# Schematic.net
KiCad netlist of a schematic drawn in Altium Designer
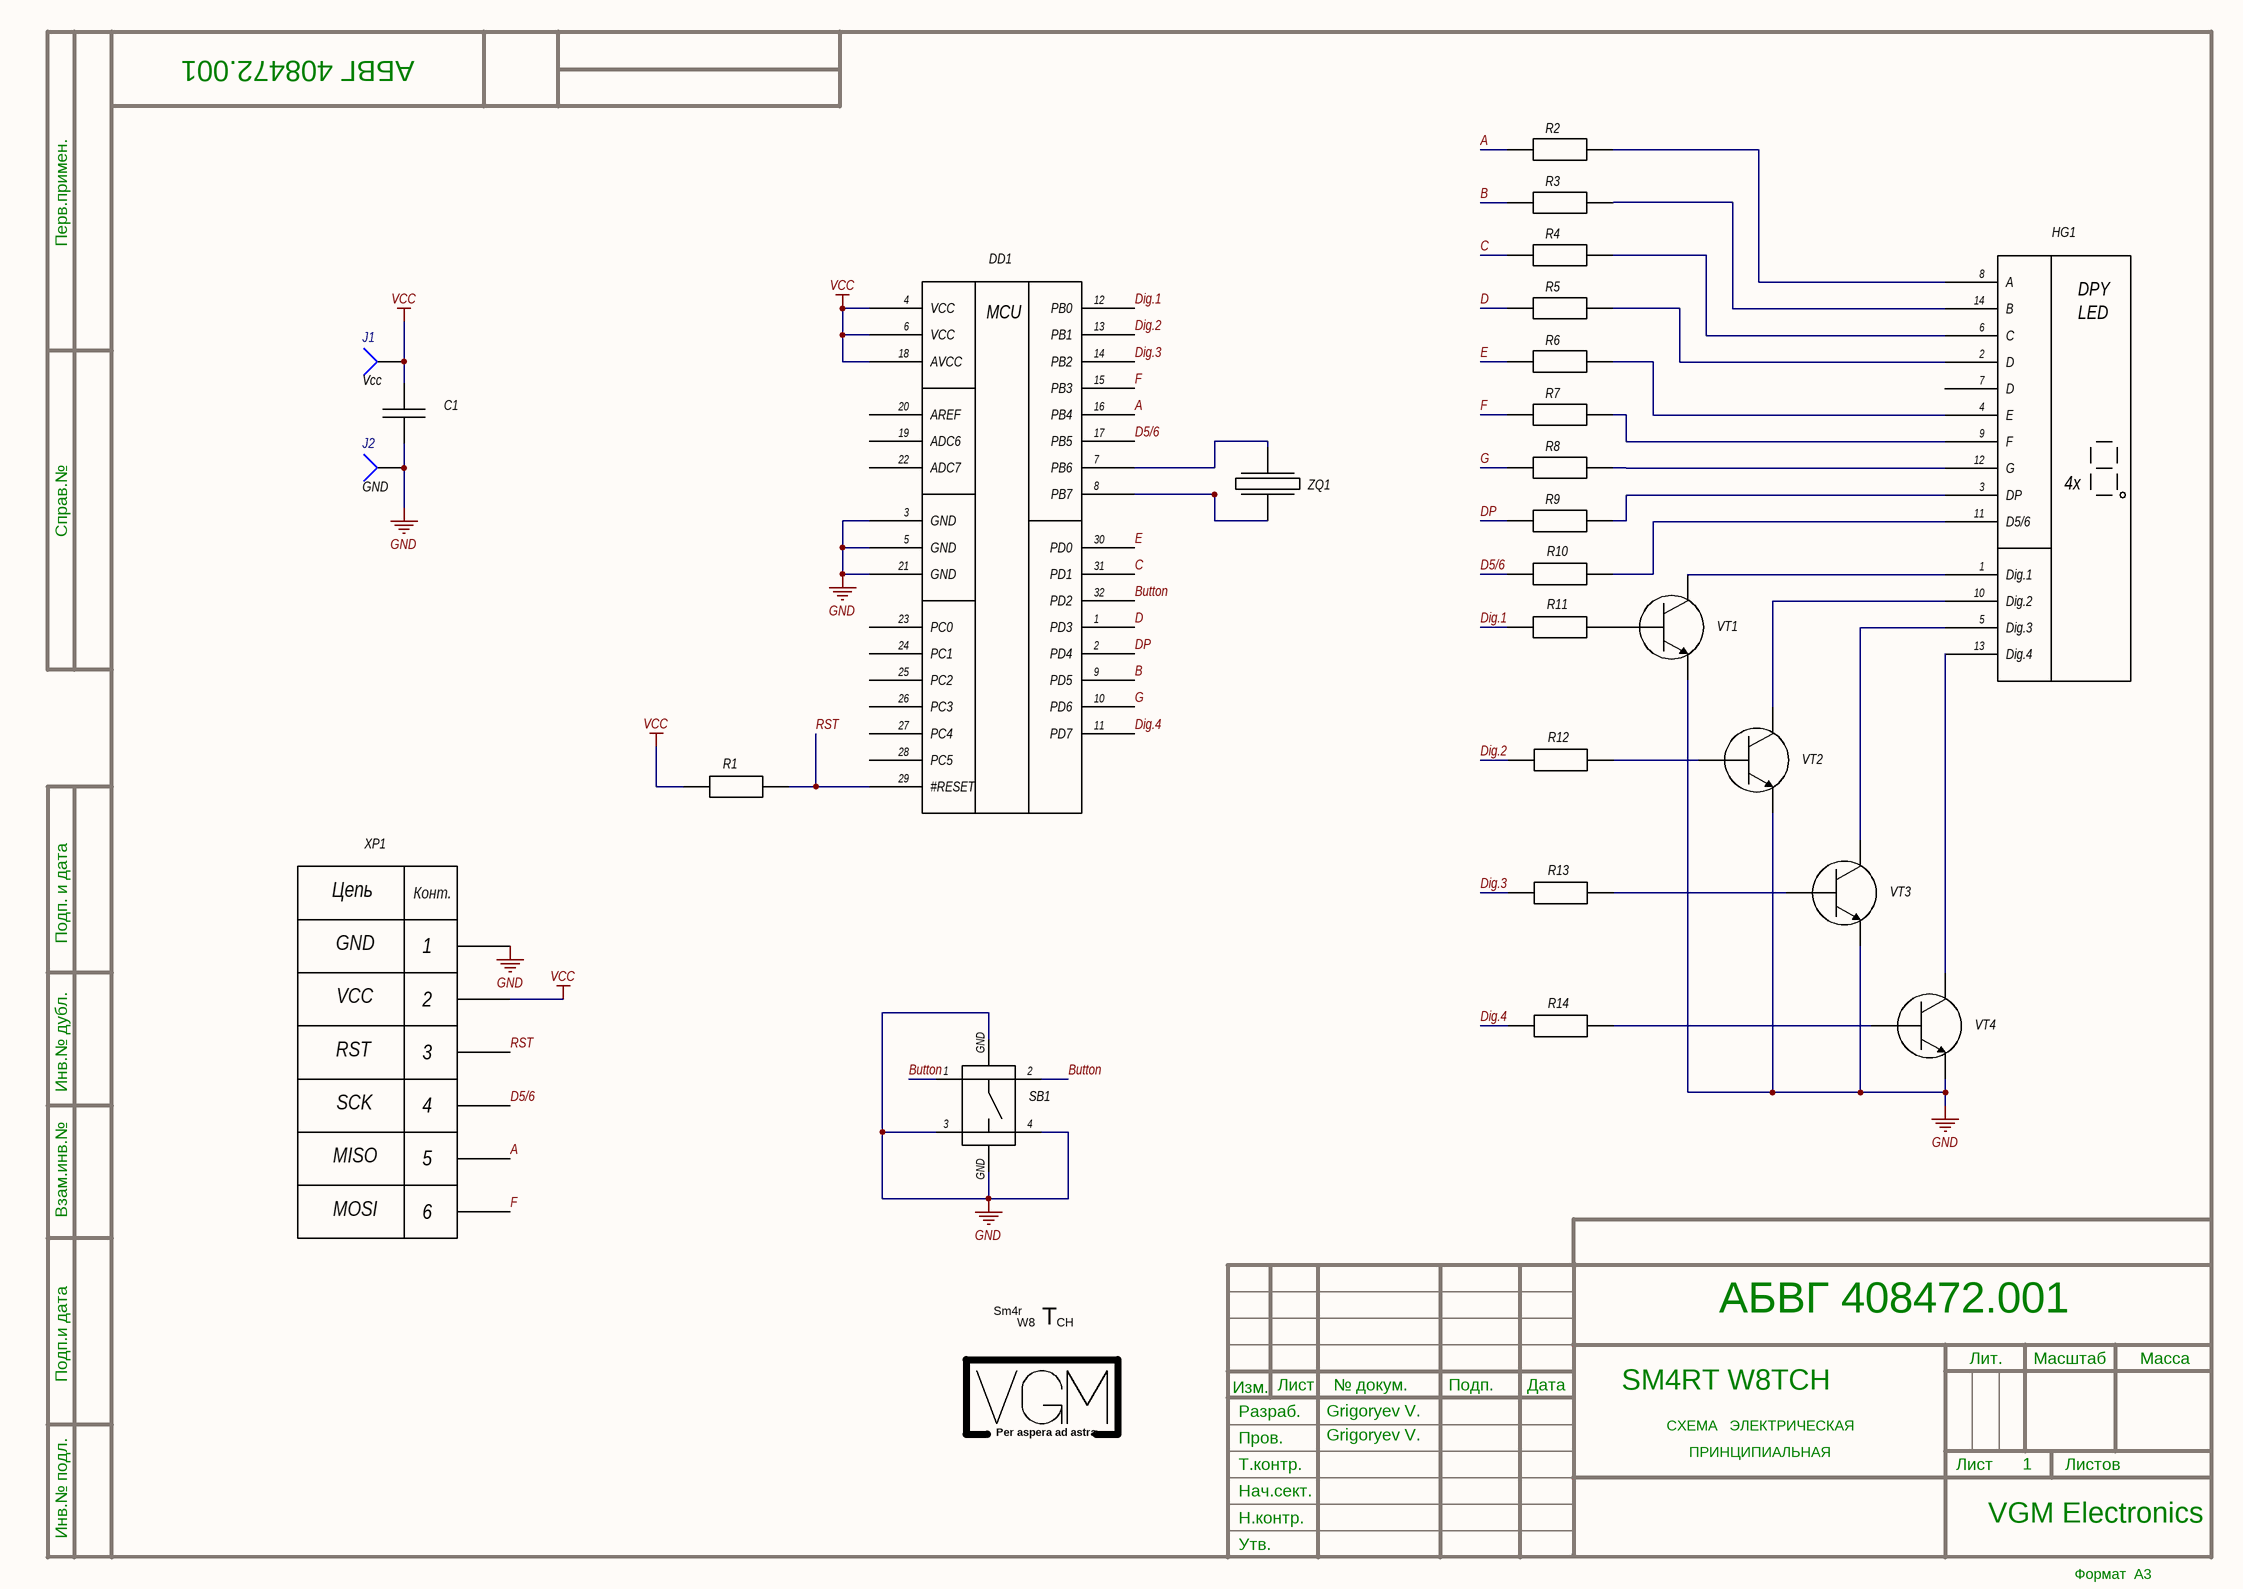
[diagram p0: Schematic.SchDoc]

(export (version "E")
  (design (tool "Eeschema 10.0.6"))
  (components
    (comp (ref "C1")
      (value "Ceramic Cap")
      (footprint "MLCC 0603 (1608)")
      (fields (field (name "PUBLISHER") "Victor Grigoryev"))
      (libsource (lib "Schlib1") (part "Ceramic Cap"))
    )
    (comp (ref "DD1")
      (value "ATmega48")
      (footprint "TQFP-32")
      (description "8-bit AVR MCU")
      (fields (field (name "PUBLISHER") "Victor Grigoryev"))
      (libsource (lib "Schlib1") (part "ATmega48"))
    )
    (comp (ref "HG1")
      (value "GNQ-2841Cx/Dx")
      (footprint "GNQ-2841Cx/Dx")
      (description "Green 7-segment display x 4")
      (fields (field (name "PUBLISHER") "Victor Grigoryev"))
      (libsource (lib "Schlib1") (part "GNQ-2841Cx/Dx"))
    )
    (comp (ref "J1")
      (value "Vcc")
      (footprint "PIN1")
      (description "Socket")
      (fields (field (name "PUBLISHER") "Altium Limited"))
      (libsource (lib "Miscellaneous Connectors") (part "Socket"))
    )
    (comp (ref "J2")
      (value "GND")
      (footprint "PIN1")
      (description "Socket")
      (fields (field (name "PUBLISHER") "Altium Limited"))
      (libsource (lib "Miscellaneous Connectors") (part "Socket"))
    )
    (comp (ref "R1")
      (value "Resistor")
      (footprint "Resistor 0603 (1208)")
      (fields (field (name "PUBLISHER") "Victor Grigoryev"))
      (libsource (lib "Schlib1") (part "Resistor"))
    )
    (comp (ref "R2")
      (value "Resistor")
      (footprint "Resistor 0603 (1208)")
      (fields (field (name "PUBLISHER") "Victor Grigoryev"))
      (libsource (lib "Schlib1") (part "Resistor"))
    )
    (comp (ref "R3")
      (value "Resistor")
      (footprint "Resistor 0603 (1208)")
      (fields (field (name "PUBLISHER") "Victor Grigoryev"))
      (libsource (lib "Schlib1") (part "Resistor"))
    )
    (comp (ref "R4")
      (value "Resistor")
      (footprint "Resistor 0603 (1208)")
      (fields (field (name "PUBLISHER") "Victor Grigoryev"))
      (libsource (lib "Schlib1") (part "Resistor"))
    )
    (comp (ref "R5")
      (value "Resistor")
      (footprint "Resistor 0603 (1208)")
      (fields (field (name "PUBLISHER") "Victor Grigoryev"))
      (libsource (lib "Schlib1") (part "Resistor"))
    )
    (comp (ref "R6")
      (value "Resistor")
      (footprint "Resistor 0603 (1208)")
      (fields (field (name "PUBLISHER") "Victor Grigoryev"))
      (libsource (lib "Schlib1") (part "Resistor"))
    )
    (comp (ref "R7")
      (value "Resistor")
      (footprint "Resistor 0603 (1208)")
      (fields (field (name "PUBLISHER") "Victor Grigoryev"))
      (libsource (lib "Schlib1") (part "Resistor"))
    )
    (comp (ref "R8")
      (value "Resistor")
      (footprint "Resistor 0603 (1208)")
      (fields (field (name "PUBLISHER") "Victor Grigoryev"))
      (libsource (lib "Schlib1") (part "Resistor"))
    )
    (comp (ref "R9")
      (value "Resistor")
      (footprint "Resistor 0603 (1208)")
      (fields (field (name "PUBLISHER") "Victor Grigoryev"))
      (libsource (lib "Schlib1") (part "Resistor"))
    )
    (comp (ref "R10")
      (value "Resistor")
      (footprint "Resistor 0603 (1208)")
      (fields (field (name "PUBLISHER") "Victor Grigoryev"))
      (libsource (lib "Schlib1") (part "Resistor"))
    )
    (comp (ref "R11")
      (value "Resistor")
      (footprint "Resistor 0603 (1208)")
      (fields (field (name "PUBLISHER") "Victor Grigoryev"))
      (libsource (lib "Schlib1") (part "Resistor"))
    )
    (comp (ref "R12")
      (value "Resistor")
      (footprint "Resistor 0603 (1208)")
      (fields (field (name "PUBLISHER") "Victor Grigoryev"))
      (libsource (lib "Schlib1") (part "Resistor"))
    )
    (comp (ref "R13")
      (value "Resistor")
      (footprint "Resistor 0603 (1208)")
      (fields (field (name "PUBLISHER") "Victor Grigoryev"))
      (libsource (lib "Schlib1") (part "Resistor"))
    )
    (comp (ref "R14")
      (value "Resistor")
      (footprint "Resistor 0603 (1208)")
      (fields (field (name "PUBLISHER") "Victor Grigoryev"))
      (libsource (lib "Schlib1") (part "Resistor"))
    )
    (comp (ref "SB1")
      (value "IT-1189UE")
      (footprint "IT-1189UE")
      (description "SMD Tact Switch")
      (fields (field (name "PUBLISHER") "Victor Grigoryev"))
      (libsource (lib "Schlib1") (part "IT-1189UE"))
    )
    (comp (ref "SM4RT W8TCH")
      (value "SM4RT W8TCH")
      (footprint "Sm4rt W8tch")
      (description "SM4RT W8TCH Logo")
      (fields (field (name "PUBLISHER") "Victor Grigoryev"))
      (libsource (lib "Schlib1") (part "SM4RT W8TCH"))
    )
    (comp (ref "VGM LOGO")
      (value "VGM Electronics Logo")
      (footprint "LOGO medium")
      (fields (field (name "PUBLISHER") "Victor Grigoryev"))
      (libsource (lib "Schlib1") (part "VGM LOGO"))
    )
    (comp (ref "VT1")
      (value "BC817-40")
      (footprint "PcbLib1:SOT-23")
      (description "NPN General Purpose Transistor")
      (fields (field (name "PUBLISHER") "Victor Grigoryev"))
      (libsource (lib "Schlib1") (part "BC817-40"))
    )
    (comp (ref "VT2")
      (value "BC817-40")
      (footprint "PcbLib1:SOT-23")
      (description "NPN General Purpose Transistor")
      (fields (field (name "PUBLISHER") "Victor Grigoryev"))
      (libsource (lib "Schlib1") (part "BC817-40"))
    )
    (comp (ref "VT3")
      (value "BC817-40")
      (footprint "PcbLib1:SOT-23")
      (description "NPN General Purpose Transistor")
      (fields (field (name "PUBLISHER") "Victor Grigoryev"))
      (libsource (lib "Schlib1") (part "BC817-40"))
    )
    (comp (ref "VT4")
      (value "BC817-40")
      (footprint "PcbLib1:SOT-23")
      (description "NPN General Purpose Transistor")
      (fields (field (name "PUBLISHER") "Victor Grigoryev"))
      (libsource (lib "Schlib1") (part "BC817-40"))
    )
    (comp (ref "XP1")
      (value "AVR Programming Pad")
      (footprint "AVR Programming Pad")
      (description "Group of pads for programming AVR MCU")
      (fields (field (name "PUBLISHER") "Victor Grigoryev"))
      (libsource (lib "Schlib1") (part "AVR Programming Pad"))
    )
    (comp (ref "ZQ1")
      (value "XTAL")
      (footprint "XTAL 32.768 kHz 0603")
      (description "Quartz Oscillator")
      (fields (field (name "PUBLISHER") "Victor Grigoryev"))
      (libsource (lib "Schlib1") (part "XTAL"))
    )
  )
  (nets
    (net (code "1") (name "/A") (class "Default")
      (node (ref "DD1") (pin "16") (pinfunction "PB4_16") (pintype "passive"))
      (node (ref "R2") (pin "1") (pinfunction "1_1") (pintype "passive"))
      (node (ref "XP1") (pin "5") (pinfunction "5_5") (pintype "passive"))
    )
    (net (code "2") (name "/B") (class "Default")
      (node (ref "DD1") (pin "9") (pinfunction "PD5_9") (pintype "passive"))
      (node (ref "R3") (pin "1") (pinfunction "1_1") (pintype "passive"))
    )
    (net (code "3") (name "/Button") (class "Default")
      (node (ref "DD1") (pin "32") (pinfunction "PD2_32") (pintype "passive"))
      (node (ref "SB1") (pin "1") (pinfunction "1_1") (pintype "passive"))
      (node (ref "SB1") (pin "2") (pinfunction "2_2") (pintype "passive"))
    )
    (net (code "4") (name "/C") (class "Default")
      (node (ref "DD1") (pin "31") (pinfunction "PD1_31") (pintype "passive"))
      (node (ref "R4") (pin "1") (pinfunction "1_1") (pintype "passive"))
    )
    (net (code "5") (name "/D") (class "Default")
      (node (ref "DD1") (pin "1") (pinfunction "PD3_1") (pintype "passive"))
      (node (ref "R5") (pin "1") (pinfunction "1_1") (pintype "passive"))
    )
    (net (code "6") (name "/D5{slash}6") (class "Default")
      (node (ref "DD1") (pin "17") (pinfunction "PB5_17") (pintype "passive"))
      (node (ref "R10") (pin "1") (pinfunction "1_1") (pintype "passive"))
      (node (ref "XP1") (pin "4") (pinfunction "4_4") (pintype "passive"))
    )
    (net (code "7") (name "/DP") (class "Default")
      (node (ref "DD1") (pin "2") (pinfunction "PD4_2") (pintype "passive"))
      (node (ref "R9") (pin "1") (pinfunction "1_1") (pintype "passive"))
    )
    (net (code "8") (name "/Dig.1") (class "Default")
      (node (ref "DD1") (pin "12") (pinfunction "PB0_12") (pintype "passive"))
      (node (ref "R11") (pin "1") (pinfunction "1_1") (pintype "passive"))
    )
    (net (code "9") (name "/Dig.2") (class "Default")
      (node (ref "DD1") (pin "13") (pinfunction "PB1_13") (pintype "passive"))
      (node (ref "R12") (pin "1") (pinfunction "1_1") (pintype "passive"))
    )
    (net (code "10") (name "/Dig.3") (class "Default")
      (node (ref "DD1") (pin "14") (pinfunction "PB2_14") (pintype "passive"))
      (node (ref "R13") (pin "1") (pinfunction "1_1") (pintype "passive"))
    )
    (net (code "11") (name "/Dig.4") (class "Default")
      (node (ref "DD1") (pin "11") (pinfunction "PD7_11") (pintype "passive"))
      (node (ref "R14") (pin "1") (pinfunction "1_1") (pintype "passive"))
    )
    (net (code "12") (name "/E") (class "Default")
      (node (ref "DD1") (pin "30") (pinfunction "PD0_30") (pintype "passive"))
      (node (ref "R6") (pin "1") (pinfunction "1_1") (pintype "passive"))
    )
    (net (code "13") (name "/F") (class "Default")
      (node (ref "DD1") (pin "15") (pinfunction "PB3_15") (pintype "passive"))
      (node (ref "R7") (pin "1") (pinfunction "1_1") (pintype "passive"))
      (node (ref "XP1") (pin "6") (pinfunction "6_6") (pintype "passive"))
    )
    (net (code "14") (name "/G") (class "Default")
      (node (ref "DD1") (pin "10") (pinfunction "PD6_10") (pintype "passive"))
      (node (ref "R8") (pin "1") (pinfunction "1_1") (pintype "passive"))
    )
    (net (code "15") (name "/RST") (class "Default")
      (node (ref "DD1") (pin "29") (pinfunction "#RESET_29") (pintype "passive"))
      (node (ref "R1") (pin "1") (pinfunction "1_1") (pintype "passive"))
      (node (ref "XP1") (pin "3") (pinfunction "3_3") (pintype "passive"))
    )
    (net (code "16") (name "GND") (class "Default")
      (node (ref "C1") (pin "1") (pintype "passive"))
      (node (ref "DD1") (pin "21") (pinfunction "GND_21") (pintype "passive"))
      (node (ref "DD1") (pin "3") (pinfunction "GND_3") (pintype "passive"))
      (node (ref "DD1") (pin "5") (pinfunction "GND_5") (pintype "passive"))
      (node (ref "J2") (pin "1") (pinfunction "1_1") (pintype "passive"))
      (node (ref "SB1") (pin "3") (pinfunction "3_3") (pintype "passive"))
      (node (ref "SB1") (pin "4") (pinfunction "4_4") (pintype "passive"))
      (node (ref "SB1") (pin "GND") (pinfunction "GND_GND") (pintype "passive"))
      (node (ref "VT1") (pin "2") (pinfunction "E_2") (pintype "passive"))
      (node (ref "VT2") (pin "2") (pinfunction "E_2") (pintype "passive"))
      (node (ref "VT3") (pin "2") (pinfunction "E_2") (pintype "passive"))
      (node (ref "VT4") (pin "2") (pinfunction "E_2") (pintype "passive"))
      (node (ref "XP1") (pin "1") (pinfunction "1_1") (pintype "passive"))
    )
    (net (code "17") (name "Net-(DD1-PB6)") (class "Default")
      (node (ref "DD1") (pin "7") (pinfunction "PB6_7") (pintype "passive"))
      (node (ref "ZQ1") (pin "2") (pintype "passive"))
    )
    (net (code "18") (name "Net-(DD1-PB7)") (class "Default")
      (node (ref "DD1") (pin "8") (pinfunction "PB7_8") (pintype "passive"))
      (node (ref "ZQ1") (pin "1") (pintype "passive"))
    )
    (net (code "19") (name "Net-(HG1-A)") (class "Default")
      (node (ref "HG1") (pin "8") (pinfunction "A_8") (pintype "passive"))
      (node (ref "R2") (pin "2") (pinfunction "2_2") (pintype "passive"))
    )
    (net (code "20") (name "Net-(HG1-B)") (class "Default")
      (node (ref "HG1") (pin "14") (pinfunction "B_14") (pintype "passive"))
      (node (ref "R3") (pin "2") (pinfunction "2_2") (pintype "passive"))
    )
    (net (code "21") (name "Net-(HG1-C)") (class "Default")
      (node (ref "HG1") (pin "6") (pinfunction "C_6") (pintype "passive"))
      (node (ref "R4") (pin "2") (pinfunction "2_2") (pintype "passive"))
    )
    (net (code "22") (name "Net-(HG1-D-Pad2)") (class "Default")
      (node (ref "HG1") (pin "2") (pinfunction "D_2") (pintype "passive"))
      (node (ref "R5") (pin "2") (pinfunction "2_2") (pintype "passive"))
    )
    (net (code "23") (name "Net-(HG1-D5{slash}6)") (class "Default")
      (node (ref "HG1") (pin "11") (pinfunction "D5/6_11") (pintype "passive"))
      (node (ref "R10") (pin "2") (pinfunction "2_2") (pintype "passive"))
    )
    (net (code "24") (name "Net-(HG1-DP)") (class "Default")
      (node (ref "HG1") (pin "3") (pinfunction "DP_3") (pintype "passive"))
      (node (ref "R9") (pin "2") (pinfunction "2_2") (pintype "passive"))
    )
    (net (code "25") (name "Net-(HG1-Dig.1)") (class "Default")
      (node (ref "HG1") (pin "1") (pinfunction "Dig.1_1") (pintype "passive"))
      (node (ref "VT1") (pin "3") (pinfunction "C_3") (pintype "passive"))
    )
    (net (code "26") (name "Net-(HG1-Dig.2)") (class "Default")
      (node (ref "HG1") (pin "10") (pinfunction "Dig.2_10") (pintype "passive"))
      (node (ref "VT2") (pin "3") (pinfunction "C_3") (pintype "passive"))
    )
    (net (code "27") (name "Net-(HG1-Dig.3)") (class "Default")
      (node (ref "HG1") (pin "5") (pinfunction "Dig.3_5") (pintype "passive"))
      (node (ref "VT3") (pin "3") (pinfunction "C_3") (pintype "passive"))
    )
    (net (code "28") (name "Net-(HG1-Dig.4)") (class "Default")
      (node (ref "HG1") (pin "13") (pinfunction "Dig.4_13") (pintype "passive"))
      (node (ref "VT4") (pin "3") (pinfunction "C_3") (pintype "passive"))
    )
    (net (code "29") (name "Net-(HG1-E)") (class "Default")
      (node (ref "HG1") (pin "4") (pinfunction "E_4") (pintype "passive"))
      (node (ref "R6") (pin "2") (pinfunction "2_2") (pintype "passive"))
    )
    (net (code "30") (name "Net-(HG1-F)") (class "Default")
      (node (ref "HG1") (pin "9") (pinfunction "F_9") (pintype "passive"))
      (node (ref "R7") (pin "2") (pinfunction "2_2") (pintype "passive"))
    )
    (net (code "31") (name "Net-(HG1-G)") (class "Default")
      (node (ref "HG1") (pin "12") (pinfunction "G_12") (pintype "passive"))
      (node (ref "R8") (pin "2") (pinfunction "2_2") (pintype "passive"))
    )
    (net (code "32") (name "Net-(VT1-B)") (class "Default")
      (node (ref "R11") (pin "2") (pinfunction "2_2") (pintype "passive"))
      (node (ref "VT1") (pin "1") (pinfunction "B_1") (pintype "passive"))
    )
    (net (code "33") (name "Net-(VT2-B)") (class "Default")
      (node (ref "R12") (pin "2") (pinfunction "2_2") (pintype "passive"))
      (node (ref "VT2") (pin "1") (pinfunction "B_1") (pintype "passive"))
    )
    (net (code "34") (name "Net-(VT3-B)") (class "Default")
      (node (ref "R13") (pin "2") (pinfunction "2_2") (pintype "passive"))
      (node (ref "VT3") (pin "1") (pinfunction "B_1") (pintype "passive"))
    )
    (net (code "35") (name "Net-(VT4-B)") (class "Default")
      (node (ref "R14") (pin "2") (pinfunction "2_2") (pintype "passive"))
      (node (ref "VT4") (pin "1") (pinfunction "B_1") (pintype "passive"))
    )
    (net (code "36") (name "VCC") (class "Default")
      (node (ref "C1") (pin "2") (pintype "passive"))
      (node (ref "DD1") (pin "18") (pinfunction "AVCC_18") (pintype "passive"))
      (node (ref "DD1") (pin "4") (pinfunction "VCC_4") (pintype "passive"))
      (node (ref "DD1") (pin "6") (pinfunction "VCC_6") (pintype "passive"))
      (node (ref "J1") (pin "1") (pinfunction "1_1") (pintype "passive"))
      (node (ref "R1") (pin "2") (pinfunction "2_2") (pintype "passive"))
      (node (ref "XP1") (pin "2") (pinfunction "2_2") (pintype "passive"))
    )
    (net (code "37") (name "unconnected-(DD1-ADC6-Pad19)") (class "Default")
      (node (ref "DD1") (pin "19") (pinfunction "ADC6_19") (pintype "passive"))
    )
    (net (code "38") (name "unconnected-(DD1-ADC7-Pad22)") (class "Default")
      (node (ref "DD1") (pin "22") (pinfunction "ADC7_22") (pintype "passive"))
    )
    (net (code "39") (name "unconnected-(DD1-AREF-Pad20)") (class "Default")
      (node (ref "DD1") (pin "20") (pinfunction "AREF_20") (pintype "passive"))
    )
    (net (code "40") (name "unconnected-(DD1-PC0-Pad23)") (class "Default")
      (node (ref "DD1") (pin "23") (pinfunction "PC0_23") (pintype "passive"))
    )
    (net (code "41") (name "unconnected-(DD1-PC1-Pad24)") (class "Default")
      (node (ref "DD1") (pin "24") (pinfunction "PC1_24") (pintype "passive"))
    )
    (net (code "42") (name "unconnected-(DD1-PC2-Pad25)") (class "Default")
      (node (ref "DD1") (pin "25") (pinfunction "PC2_25") (pintype "passive"))
    )
    (net (code "43") (name "unconnected-(DD1-PC3-Pad26)") (class "Default")
      (node (ref "DD1") (pin "26") (pinfunction "PC3_26") (pintype "passive"))
    )
    (net (code "44") (name "unconnected-(DD1-PC4-Pad27)") (class "Default")
      (node (ref "DD1") (pin "27") (pinfunction "PC4_27") (pintype "passive"))
    )
    (net (code "45") (name "unconnected-(DD1-PC5-Pad28)") (class "Default")
      (node (ref "DD1") (pin "28") (pinfunction "PC5_28") (pintype "passive"))
    )
    (net (code "46") (name "unconnected-(HG1-D-Pad7)") (class "Default")
      (node (ref "HG1") (pin "7") (pinfunction "D_7") (pintype "passive"))
    )
  )
)
